# working.net
KiCad netlist of a schematic drawn in EAGLE
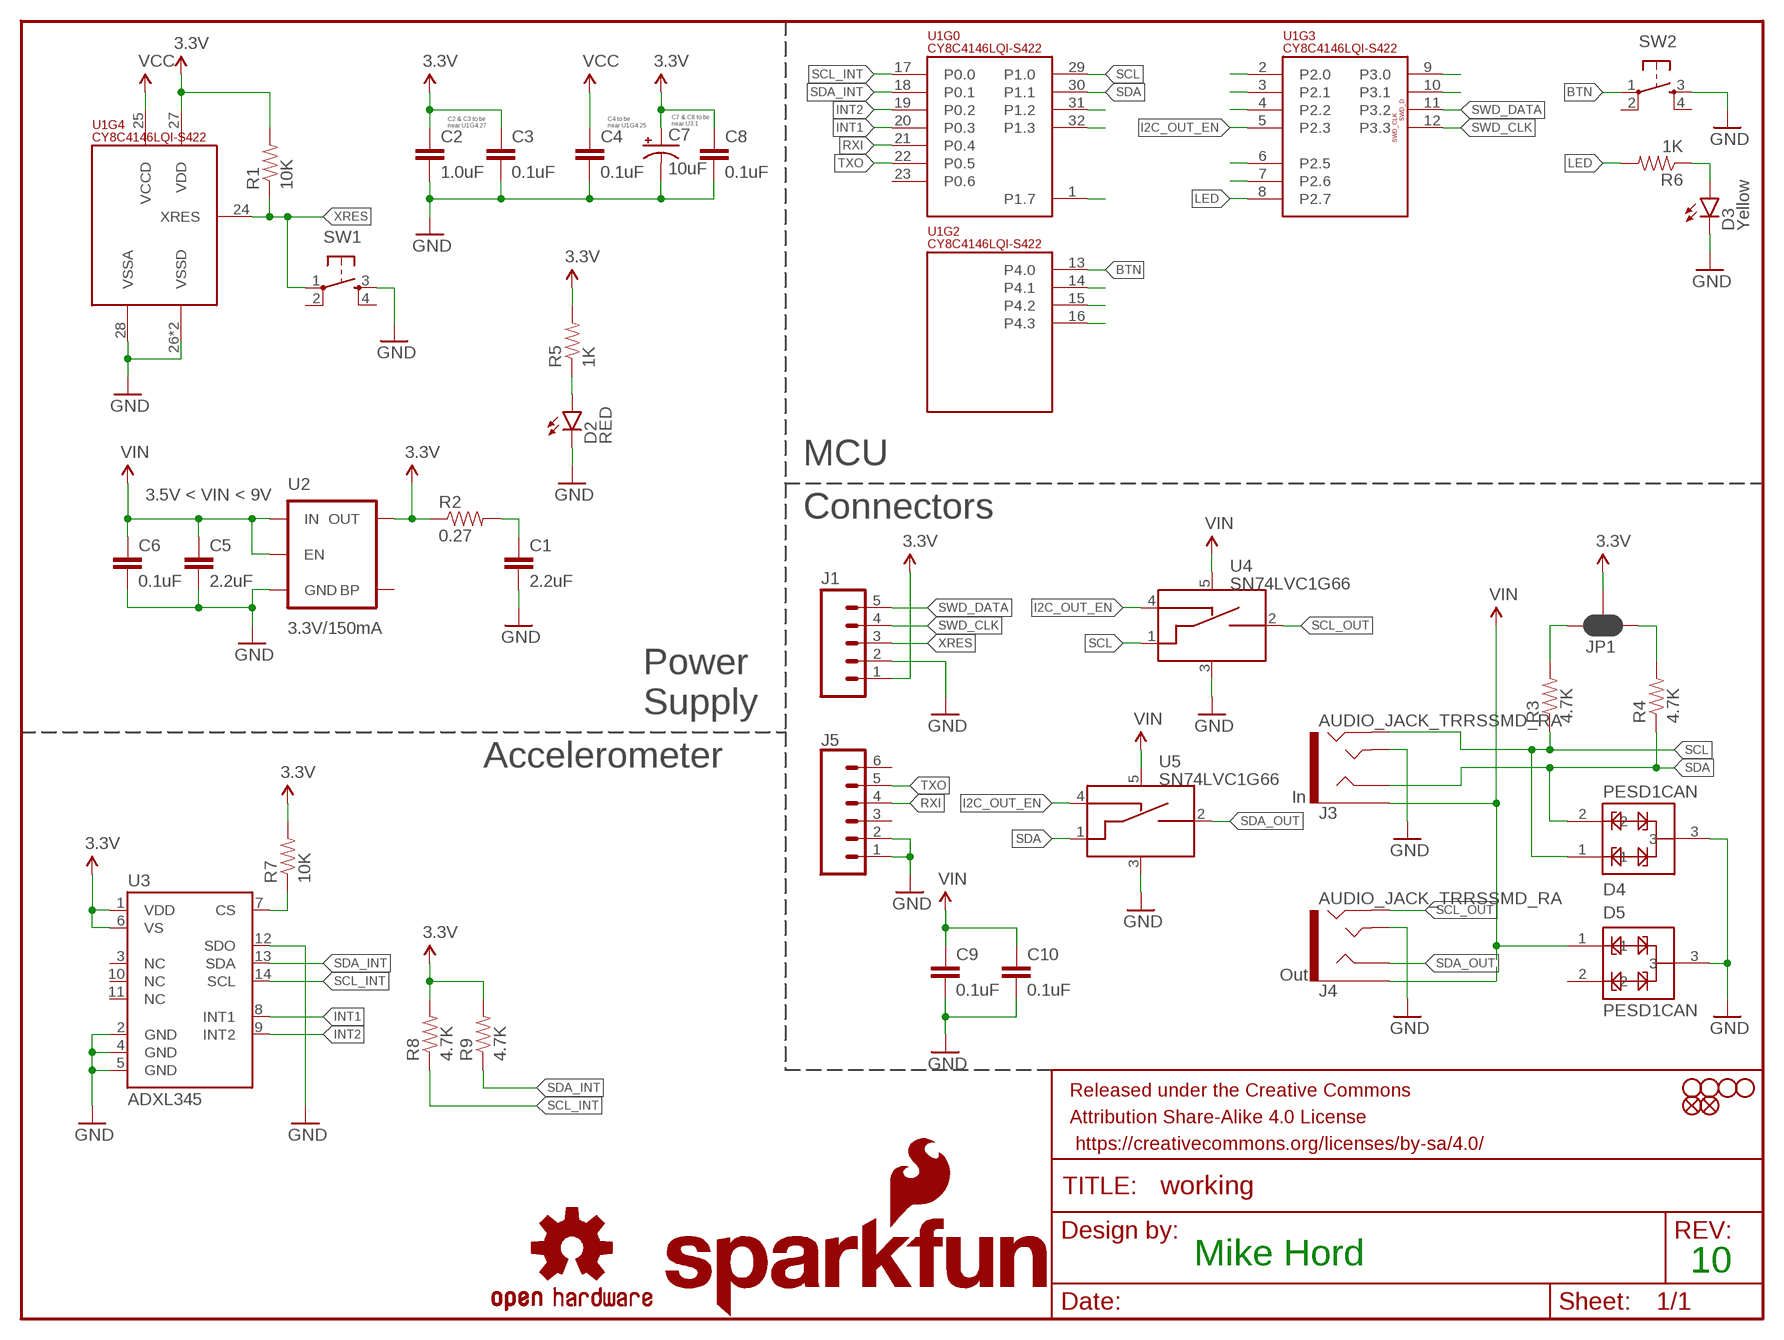
[diagram p0: schematic, sheet 1]

(export (version "E")
  (design (tool "Eeschema 10.0.6"))
  (components
    (comp (ref "C1")
      (value "2.2uF")
      (footprint "eagle-import:0603-CAP")
      (libsource (lib "eagle-import") (part "2.2UF-10V-20%(0603)"))
    )
    (comp (ref "C2")
      (value "1.0uF")
      (footprint "eagle-import:0402-CAP")
      (libsource (lib "eagle-import") (part "1.0UF-16V-10%(0402)"))
    )
    (comp (ref "C3")
      (value "0.1uF")
      (footprint "eagle-import:0402-CAP")
      (libsource (lib "eagle-import") (part "0.1UF-16V(+-10%)(0402)"))
    )
    (comp (ref "C4")
      (value "0.1uF")
      (footprint "eagle-import:0402-CAP")
      (libsource (lib "eagle-import") (part "0.1UF-16V(+-10%)(0402)"))
    )
    (comp (ref "C5")
      (value "2.2uF")
      (footprint "eagle-import:0603-CAP")
      (libsource (lib "eagle-import") (part "2.2UF-10V-20%(0603)"))
    )
    (comp (ref "C6")
      (value "0.1uF")
      (footprint "eagle-import:0402-CAP")
      (libsource (lib "eagle-import") (part "0.1UF-16V(+-10%)(0402)"))
    )
    (comp (ref "C7")
      (value "10uF")
      (footprint "eagle-import:EIA3216")
      (libsource (lib "eagle-import") (part "10UF-16V-10%(TANT)"))
    )
    (comp (ref "C8")
      (value "0.1uF")
      (footprint "eagle-import:0402-CAP")
      (libsource (lib "eagle-import") (part "0.1UF-16V(+-10%)(0402)"))
    )
    (comp (ref "C9")
      (value "0.1uF")
      (footprint "eagle-import:0402-CAP")
      (libsource (lib "eagle-import") (part "0.1UF-16V(+-10%)(0402)"))
    )
    (comp (ref "C10")
      (value "0.1uF")
      (footprint "eagle-import:0402-CAP")
      (libsource (lib "eagle-import") (part "0.1UF-16V(+-10%)(0402)"))
    )
    (comp (ref "D2")
      (value "RED")
      (footprint "eagle-import:LED-0603")
      (libsource (lib "eagle-import") (part "LED-RED0603"))
    )
    (comp (ref "D3")
      (value "Yellow")
      (footprint "eagle-import:LED-0603")
      (libsource (lib "eagle-import") (part "LED-YELLOW0603-SMART"))
    )
    (comp (ref "D4")
      (value "PESD1CAN")
      (footprint "eagle-import:SOT23-3")
      (libsource (lib "eagle-import") (part "PESD1CAN"))
    )
    (comp (ref "D5")
      (value "PESD1CAN")
      (footprint "eagle-import:SOT23-3")
      (libsource (lib "eagle-import") (part "PESD1CAN"))
    )
    (comp (ref "FD1")
      (value "FIDUCIALUFIDUCIAL")
      (footprint "eagle-import:MICRO-FIDUCIAL")
      (libsource (lib "eagle-import") (part "FIDUCIALUFIDUCIAL"))
    )
    (comp (ref "FD2")
      (value "FIDUCIALUFIDUCIAL")
      (footprint "eagle-import:MICRO-FIDUCIAL")
      (libsource (lib "eagle-import") (part "FIDUCIALUFIDUCIAL"))
    )
    (comp (ref "FRAME1")
      (value "FRAME-LETTER")
      (footprint "eagle-import:CREATIVE_COMMONS")
      (libsource (lib "eagle-import") (part "FRAME-LETTER"))
    )
    (comp (ref "H1")
      (value "STAND-OFF")
      (footprint "eagle-import:STAND-OFF")
      (libsource (lib "eagle-import") (part "STAND-OFF"))
    )
    (comp (ref "H2")
      (value "STAND-OFF")
      (footprint "eagle-import:STAND-OFF")
      (libsource (lib "eagle-import") (part "STAND-OFF"))
    )
    (comp (ref "H3")
      (value "STAND-OFF")
      (footprint "eagle-import:STAND-OFF")
      (libsource (lib "eagle-import") (part "STAND-OFF"))
    )
    (comp (ref "H4")
      (value "STAND-OFF")
      (footprint "eagle-import:STAND-OFF")
      (libsource (lib "eagle-import") (part "STAND-OFF"))
    )
    (comp (ref "J1")
      (value "M05NO_SILK")
      (footprint "eagle-import:1X05_NO_SILK")
      (libsource (lib "eagle-import") (part "M05NO_SILK"))
    )
    (comp (ref "J3")
      (value "AUDIO_JACK_TRRSSMD_RA")
      (footprint "eagle-import:AUDIO_JACK_3.5MM_TRRS_SMD_RA")
      (libsource (lib "eagle-import") (part "AUDIO_JACK_TRRSSMD_RA"))
    )
    (comp (ref "J4")
      (value "AUDIO_JACK_TRRSSMD_RA")
      (footprint "eagle-import:AUDIO_JACK_3.5MM_TRRS_SMD_RA")
      (libsource (lib "eagle-import") (part "AUDIO_JACK_TRRSSMD_RA"))
    )
    (comp (ref "J5")
      (value "CONN_06NO_SILK_NO_POP")
      (footprint "eagle-import:1X06_NO_SILK")
      (libsource (lib "eagle-import") (part "CONN_06NO_SILK_NO_POP"))
    )
    (comp (ref "JP1")
      (value "JUMPER-PAD-3-NC_BY_PASTE")
      (footprint "eagle-import:PAD-JUMPER-3-NC_BY_PASTE_YES_SILK_FULL_BOX")
      (libsource (lib "eagle-import") (part "JUMPER-PAD-3-NC_BY_PASTE"))
    )
    (comp (ref "LOGO1")
      (value "SFE_LOGO_NAME_FLAME.1_INCH")
      (footprint "eagle-import:SFE_LOGO_NAME_FLAME_.1")
      (libsource (lib "eagle-import") (part "SFE_LOGO_NAME_FLAME.1_INCH"))
    )
    (comp (ref "LOGO2")
      (value "OSHW-LOGOS")
      (footprint "eagle-import:OSHW-LOGO-S")
      (libsource (lib "eagle-import") (part "OSHW-LOGOS"))
    )
    (comp (ref "LOGO3")
      (value "OSHW-LOGOS")
      (footprint "eagle-import:OSHW-LOGO-S")
      (libsource (lib "eagle-import") (part "OSHW-LOGOS"))
    )
    (comp (ref "LOGO4")
      (value "SFE_LOGO_NAME_FLAME.1_INCH")
      (footprint "eagle-import:SFE_LOGO_NAME_FLAME_.1")
      (libsource (lib "eagle-import") (part "SFE_LOGO_NAME_FLAME.1_INCH"))
    )
    (comp (ref "R1")
      (value "10K")
      (footprint "eagle-import:0603-RES")
      (libsource (lib "eagle-import") (part "10KOHM-1/10W-1%(0603)0603"))
    )
    (comp (ref "R2")
      (value "0.27")
      (footprint "eagle-import:0603-RES")
      (libsource (lib "eagle-import") (part "0.27OHM-1/10W-1%(0603)"))
    )
    (comp (ref "R3")
      (value "4.7K")
      (footprint "eagle-import:0603-RES")
      (libsource (lib "eagle-import") (part "4.7KOHM-1/10W-1%(0603)"))
    )
    (comp (ref "R4")
      (value "4.7K")
      (footprint "eagle-import:0603-RES")
      (libsource (lib "eagle-import") (part "4.7KOHM-1/10W-1%(0603)"))
    )
    (comp (ref "R5")
      (value "1K")
      (footprint "eagle-import:0603-RES")
      (libsource (lib "eagle-import") (part "1KOHM-1/10W-1%(0603)"))
    )
    (comp (ref "R6")
      (value "1K")
      (footprint "eagle-import:0603-RES")
      (libsource (lib "eagle-import") (part "1KOHM-1/10W-1%(0603)"))
    )
    (comp (ref "R7")
      (value "10K")
      (footprint "eagle-import:0603-RES")
      (libsource (lib "eagle-import") (part "10KOHM-1/10W-1%(0603)0603"))
    )
    (comp (ref "R8")
      (value "4.7K")
      (footprint "eagle-import:0603-RES")
      (libsource (lib "eagle-import") (part "4.7KOHM-1/10W-1%(0603)"))
    )
    (comp (ref "R9")
      (value "4.7K")
      (footprint "eagle-import:0603-RES")
      (libsource (lib "eagle-import") (part "4.7KOHM-1/10W-1%(0603)"))
    )
    (comp (ref "SW1")
      (value "SWITCH_SPST_4_PINRECT")
      (footprint "eagle-import:TACTILE_SWITCH_SMD_4.6X2.8MM")
      (libsource (lib "eagle-import") (part "SWITCH_SPST_4_PINRECT"))
    )
    (comp (ref "SW2")
      (value "SWITCH_SPST_4_PINRECT")
      (footprint "eagle-import:TACTILE_SWITCH_SMD_4.6X2.8MM")
      (libsource (lib "eagle-import") (part "SWITCH_SPST_4_PINRECT"))
    )
    (comp (ref "U1")
      (value "CY8C4146LQI-S422")
      (footprint "eagle-import:QFN-32")
      (libsource (lib "eagle-import") (part "PSOC4_4100S_32QFN"))
    )
    (comp (ref "U2")
      (value "3.3V/150mA")
      (footprint "eagle-import:SOT23-5")
      (libsource (lib "eagle-import") (part "V_REG_MIC52053.3V"))
    )
    (comp (ref "U3")
      (value "ADXL345")
      (footprint "eagle-import:ADXL3451_1")
      (libsource (lib "eagle-import") (part "ADXL345{dblquote}"))
    )
    (comp (ref "U4")
      (value "SN74LVC1G66")
      (footprint "eagle-import:SOT23-5")
      (libsource (lib "eagle-import") (part "SN74LVC1G66_SPST_AMUX"))
    )
    (comp (ref "U5")
      (value "SN74LVC1G66")
      (footprint "eagle-import:SOT23-5")
      (libsource (lib "eagle-import") (part "SN74LVC1G66_SPST_AMUX"))
    )
  )
  (nets
    (net (code "1") (name "3.3V") (class "Default")
      (node (ref "C2") (pin "1") (pinfunction "1_1") (pintype "passive"))
      (node (ref "C3") (pin "1") (pinfunction "1_1") (pintype "passive"))
      (node (ref "C7") (pin "A") (pinfunction "+_A") (pintype "passive"))
      (node (ref "C8") (pin "1") (pinfunction "1_1") (pintype "passive"))
      (node (ref "J1") (pin "1") (pinfunction "1_1") (pintype "passive"))
      (node (ref "JP1") (pin "2") (pinfunction "2_2") (pintype "passive"))
      (node (ref "R1") (pin "2") (pinfunction "2_2") (pintype "passive"))
      (node (ref "R2") (pin "1") (pinfunction "1_1") (pintype "passive"))
      (node (ref "R5") (pin "2") (pinfunction "2_2") (pintype "passive"))
      (node (ref "R7") (pin "2") (pinfunction "2_2") (pintype "passive"))
      (node (ref "R8") (pin "2") (pinfunction "2_2") (pintype "passive"))
      (node (ref "R9") (pin "2") (pinfunction "2_2") (pintype "passive"))
      (node (ref "U1") (pin "27") (pinfunction "VDD_27") (pintype "bidirectional"))
      (node (ref "U2") (pin "5") (pinfunction "OUT_5") (pintype "passive"))
      (node (ref "U3") (pin "1") (pinfunction "VDD_1") (pintype "bidirectional"))
      (node (ref "U3") (pin "6") (pinfunction "VS_6") (pintype "bidirectional"))
    )
    (net (code "2") (name "BTN") (class "Default")
      (node (ref "SW2") (pin "1") (pinfunction "1_1") (pintype "passive"))
      (node (ref "U1") (pin "13") (pinfunction "P4.0_13") (pintype "bidirectional"))
    )
    (net (code "3") (name "GND") (class "Default")
      (node (ref "C1") (pin "2") (pinfunction "2_2") (pintype "passive"))
      (node (ref "C10") (pin "2") (pinfunction "2_2") (pintype "passive"))
      (node (ref "C2") (pin "2") (pinfunction "2_2") (pintype "passive"))
      (node (ref "C3") (pin "2") (pinfunction "2_2") (pintype "passive"))
      (node (ref "C4") (pin "2") (pinfunction "2_2") (pintype "passive"))
      (node (ref "C5") (pin "2") (pinfunction "2_2") (pintype "passive"))
      (node (ref "C6") (pin "2") (pinfunction "2_2") (pintype "passive"))
      (node (ref "C7") (pin "C") (pinfunction "-_C") (pintype "passive"))
      (node (ref "C8") (pin "2") (pinfunction "2_2") (pintype "passive"))
      (node (ref "C9") (pin "2") (pinfunction "2_2") (pintype "passive"))
      (node (ref "D2") (pin "C") (pinfunction "C_C") (pintype "passive"))
      (node (ref "D3") (pin "C") (pinfunction "C_C") (pintype "passive"))
      (node (ref "D4") (pin "3") (pinfunction "3_3") (pintype "bidirectional"))
      (node (ref "D5") (pin "3") (pinfunction "3_3") (pintype "bidirectional"))
      (node (ref "J1") (pin "2") (pinfunction "2_2") (pintype "passive"))
      (node (ref "J3") (pin "TIP") (pinfunction "TIP_TIP") (pintype "bidirectional"))
      (node (ref "J4") (pin "TIP") (pinfunction "TIP_TIP") (pintype "bidirectional"))
      (node (ref "J5") (pin "1") (pinfunction "1_1") (pintype "passive"))
      (node (ref "J5") (pin "2") (pinfunction "2_2") (pintype "passive"))
      (node (ref "SW1") (pin "3") (pinfunction "3_3") (pintype "passive"))
      (node (ref "SW2") (pin "3") (pinfunction "3_3") (pintype "passive"))
      (node (ref "U1") (pin "26") (pinfunction "VSSD_26") (pintype "bidirectional"))
      (node (ref "U1") (pin "28") (pinfunction "VSSA_28") (pintype "bidirectional"))
      (node (ref "U1") (pin "EP") (pinfunction "VSSD_EP") (pintype "bidirectional"))
      (node (ref "U2") (pin "2") (pinfunction "GND_2") (pintype "input"))
      (node (ref "U3") (pin "12") (pinfunction "SDO_12") (pintype "bidirectional"))
      (node (ref "U3") (pin "2") (pinfunction "GND_2") (pintype "bidirectional"))
      (node (ref "U3") (pin "4") (pinfunction "GND_4") (pintype "bidirectional"))
      (node (ref "U3") (pin "5") (pinfunction "GND_5") (pintype "bidirectional"))
      (node (ref "U4") (pin "3") (pinfunction "VSS_3") (pintype "bidirectional"))
      (node (ref "U5") (pin "3") (pinfunction "VSS_3") (pintype "bidirectional"))
    )
    (net (code "4") (name "I2C_OUT_EN") (class "Default")
      (node (ref "U1") (pin "5") (pinfunction "P2.3_5") (pintype "bidirectional"))
      (node (ref "U4") (pin "4") (pinfunction "CTRL_IN_4") (pintype "bidirectional"))
      (node (ref "U5") (pin "4") (pinfunction "CTRL_IN_4") (pintype "bidirectional"))
    )
    (net (code "5") (name "INT1") (class "Default")
      (node (ref "U1") (pin "20") (pinfunction "P0.3_20") (pintype "bidirectional"))
      (node (ref "U3") (pin "8") (pinfunction "INT1_8") (pintype "bidirectional"))
    )
    (net (code "6") (name "INT2") (class "Default")
      (node (ref "U1") (pin "19") (pinfunction "P0.2_19") (pintype "bidirectional"))
      (node (ref "U3") (pin "9") (pinfunction "INT2_9") (pintype "bidirectional"))
    )
    (net (code "7") (name "LED") (class "Default")
      (node (ref "R6") (pin "2") (pinfunction "2_2") (pintype "passive"))
      (node (ref "U1") (pin "8") (pinfunction "P2.7_8") (pintype "bidirectional"))
    )
    (net (code "8") (name "Net-(C1-Pad1)") (class "Default")
      (node (ref "C1") (pin "1") (pinfunction "1_1") (pintype "passive"))
      (node (ref "R2") (pin "2") (pinfunction "2_2") (pintype "passive"))
    )
    (net (code "9") (name "Net-(D2-PadA)") (class "Default")
      (node (ref "D2") (pin "A") (pinfunction "A_A") (pintype "passive"))
      (node (ref "R5") (pin "1") (pinfunction "1_1") (pintype "passive"))
    )
    (net (code "10") (name "Net-(D3-PadA)") (class "Default")
      (node (ref "D3") (pin "A") (pinfunction "A_A") (pintype "passive"))
      (node (ref "R6") (pin "1") (pinfunction "1_1") (pintype "passive"))
    )
    (net (code "11") (name "Net-(JP1-Pad1)") (class "Default")
      (node (ref "JP1") (pin "1") (pinfunction "1_1") (pintype "passive"))
      (node (ref "R4") (pin "2") (pinfunction "2_2") (pintype "passive"))
    )
    (net (code "12") (name "Net-(JP1-Pad3)") (class "Default")
      (node (ref "JP1") (pin "3") (pinfunction "3_3") (pintype "passive"))
      (node (ref "R3") (pin "2") (pinfunction "2_2") (pintype "passive"))
    )
    (net (code "13") (name "Net-(U3-CS)") (class "Default")
      (node (ref "R7") (pin "1") (pinfunction "1_1") (pintype "passive"))
      (node (ref "U3") (pin "7") (pinfunction "CS_7") (pintype "bidirectional"))
    )
    (net (code "14") (name "RXI") (class "Default")
      (node (ref "J5") (pin "4") (pinfunction "4_4") (pintype "passive"))
      (node (ref "U1") (pin "21") (pinfunction "P0.4_21") (pintype "bidirectional"))
    )
    (net (code "15") (name "SCL") (class "Default")
      (node (ref "D4") (pin "1") (pinfunction "1_1") (pintype "bidirectional"))
      (node (ref "J3") (pin "RING2") (pinfunction "RING2_RING2") (pintype "bidirectional"))
      (node (ref "R3") (pin "1") (pinfunction "1_1") (pintype "passive"))
      (node (ref "U1") (pin "29") (pinfunction "P1.0_29") (pintype "bidirectional"))
      (node (ref "U4") (pin "1") (pinfunction "A_IN_1") (pintype "bidirectional"))
    )
    (net (code "16") (name "SCL_INT") (class "Default")
      (node (ref "R8") (pin "1") (pinfunction "1_1") (pintype "passive"))
      (node (ref "U1") (pin "17") (pinfunction "P0.0_17") (pintype "bidirectional"))
      (node (ref "U3") (pin "14") (pinfunction "SCL_14") (pintype "bidirectional"))
    )
    (net (code "17") (name "SCL_OUT") (class "Default")
      (node (ref "J4") (pin "RING2") (pinfunction "RING2_RING2") (pintype "bidirectional"))
      (node (ref "U4") (pin "2") (pinfunction "A_OUT_2") (pintype "bidirectional"))
    )
    (net (code "18") (name "SDA") (class "Default")
      (node (ref "D4") (pin "2") (pinfunction "2_2") (pintype "bidirectional"))
      (node (ref "J3") (pin "RING1") (pinfunction "RING1_RING1") (pintype "bidirectional"))
      (node (ref "R4") (pin "1") (pinfunction "1_1") (pintype "passive"))
      (node (ref "U1") (pin "30") (pinfunction "P1.1_30") (pintype "bidirectional"))
      (node (ref "U5") (pin "1") (pinfunction "A_IN_1") (pintype "bidirectional"))
    )
    (net (code "19") (name "SDA_INT") (class "Default")
      (node (ref "R9") (pin "1") (pinfunction "1_1") (pintype "passive"))
      (node (ref "U1") (pin "18") (pinfunction "P0.1_18") (pintype "bidirectional"))
      (node (ref "U3") (pin "13") (pinfunction "SDA_13") (pintype "bidirectional"))
    )
    (net (code "20") (name "SDA_OUT") (class "Default")
      (node (ref "J4") (pin "RING1") (pinfunction "RING1_RING1") (pintype "bidirectional"))
      (node (ref "U5") (pin "2") (pinfunction "A_OUT_2") (pintype "bidirectional"))
    )
    (net (code "21") (name "SWD_CLK") (class "Default")
      (node (ref "J1") (pin "4") (pinfunction "4_4") (pintype "passive"))
      (node (ref "U1") (pin "12") (pinfunction "P3.3_12") (pintype "bidirectional"))
    )
    (net (code "22") (name "SWD_DATA") (class "Default")
      (node (ref "J1") (pin "5") (pinfunction "5_5") (pintype "passive"))
      (node (ref "U1") (pin "11") (pinfunction "P3.2_11") (pintype "bidirectional"))
    )
    (net (code "23") (name "TXO") (class "Default")
      (node (ref "J5") (pin "5") (pinfunction "5_5") (pintype "passive"))
      (node (ref "U1") (pin "22") (pinfunction "P0.5_22") (pintype "bidirectional"))
    )
    (net (code "24") (name "VCC") (class "Default")
      (node (ref "C4") (pin "1") (pinfunction "1_1") (pintype "passive"))
      (node (ref "U1") (pin "25") (pinfunction "VCCD_25") (pintype "bidirectional"))
    )
    (net (code "25") (name "VIN") (class "Default")
      (node (ref "C10") (pin "1") (pinfunction "1_1") (pintype "passive"))
      (node (ref "C5") (pin "1") (pinfunction "1_1") (pintype "passive"))
      (node (ref "C6") (pin "1") (pinfunction "1_1") (pintype "passive"))
      (node (ref "C9") (pin "1") (pinfunction "1_1") (pintype "passive"))
      (node (ref "D5") (pin "1") (pinfunction "1_1") (pintype "bidirectional"))
      (node (ref "J3") (pin "EARTH") (pinfunction "EARTH_EARTH") (pintype "bidirectional"))
      (node (ref "J4") (pin "EARTH") (pinfunction "EARTH_EARTH") (pintype "bidirectional"))
      (node (ref "U2") (pin "1") (pinfunction "IN_1") (pintype "input"))
      (node (ref "U2") (pin "3") (pinfunction "EN_3") (pintype "input"))
      (node (ref "U4") (pin "5") (pinfunction "VCC_5") (pintype "bidirectional"))
      (node (ref "U5") (pin "5") (pinfunction "VCC_5") (pintype "bidirectional"))
    )
    (net (code "26") (name "XRES") (class "Default")
      (node (ref "J1") (pin "3") (pinfunction "3_3") (pintype "passive"))
      (node (ref "R1") (pin "1") (pinfunction "1_1") (pintype "passive"))
      (node (ref "SW1") (pin "1") (pinfunction "1_1") (pintype "passive"))
      (node (ref "U1") (pin "24") (pinfunction "XRES_24") (pintype "bidirectional"))
    )
    (net (code "27") (name "unconnected-(D5-Pad2)") (class "Default")
      (node (ref "D5") (pin "2") (pinfunction "2_2") (pintype "bidirectional"))
    )
    (net (code "28") (name "unconnected-(J5-Pad3)") (class "Default")
      (node (ref "J5") (pin "3") (pinfunction "3_3") (pintype "passive"))
    )
    (net (code "29") (name "unconnected-(J5-Pad6)") (class "Default")
      (node (ref "J5") (pin "6") (pinfunction "6_6") (pintype "passive"))
    )
    (net (code "30") (name "unconnected-(SW1-Pad2)") (class "Default")
      (node (ref "SW1") (pin "2") (pinfunction "2_2") (pintype "passive"))
    )
    (net (code "31") (name "unconnected-(SW1-Pad4)") (class "Default")
      (node (ref "SW1") (pin "4") (pinfunction "4_4") (pintype "passive"))
    )
    (net (code "32") (name "unconnected-(SW2-Pad2)") (class "Default")
      (node (ref "SW2") (pin "2") (pinfunction "2_2") (pintype "passive"))
    )
    (net (code "33") (name "unconnected-(SW2-Pad4)") (class "Default")
      (node (ref "SW2") (pin "4") (pinfunction "4_4") (pintype "passive"))
    )
    (net (code "34") (name "unconnected-(U1A-P0.6-Pad23)") (class "Default")
      (node (ref "U1") (pin "23") (pinfunction "P0.6_23") (pintype "bidirectional"))
    )
    (net (code "35") (name "unconnected-(U1A-P1.2-Pad31)") (class "Default")
      (node (ref "U1") (pin "31") (pinfunction "P1.2_31") (pintype "bidirectional"))
    )
    (net (code "36") (name "unconnected-(U1A-P1.3-Pad32)") (class "Default")
      (node (ref "U1") (pin "32") (pinfunction "P1.3_32") (pintype "bidirectional"))
    )
    (net (code "37") (name "unconnected-(U1A-P1.7-Pad1)") (class "Default")
      (node (ref "U1") (pin "1") (pinfunction "P1.7_1") (pintype "bidirectional"))
    )
    (net (code "38") (name "unconnected-(U1B-P4.1-Pad14)") (class "Default")
      (node (ref "U1") (pin "14") (pinfunction "P4.1_14") (pintype "bidirectional"))
    )
    (net (code "39") (name "unconnected-(U1B-P4.2-Pad15)") (class "Default")
      (node (ref "U1") (pin "15") (pinfunction "P4.2_15") (pintype "bidirectional"))
    )
    (net (code "40") (name "unconnected-(U1B-P4.3-Pad16)") (class "Default")
      (node (ref "U1") (pin "16") (pinfunction "P4.3_16") (pintype "bidirectional"))
    )
    (net (code "41") (name "unconnected-(U1C-P2.0-Pad2)") (class "Default")
      (node (ref "U1") (pin "2") (pinfunction "P2.0_2") (pintype "bidirectional"))
    )
    (net (code "42") (name "unconnected-(U1C-P2.1-Pad3)") (class "Default")
      (node (ref "U1") (pin "3") (pinfunction "P2.1_3") (pintype "bidirectional"))
    )
    (net (code "43") (name "unconnected-(U1C-P2.2-Pad4)") (class "Default")
      (node (ref "U1") (pin "4") (pinfunction "P2.2_4") (pintype "bidirectional"))
    )
    (net (code "44") (name "unconnected-(U1C-P2.5-Pad6)") (class "Default")
      (node (ref "U1") (pin "6") (pinfunction "P2.5_6") (pintype "bidirectional"))
    )
    (net (code "45") (name "unconnected-(U1C-P2.6-Pad7)") (class "Default")
      (node (ref "U1") (pin "7") (pinfunction "P2.6_7") (pintype "bidirectional"))
    )
    (net (code "46") (name "unconnected-(U1C-P3.0-Pad9)") (class "Default")
      (node (ref "U1") (pin "9") (pinfunction "P3.0_9") (pintype "bidirectional"))
    )
    (net (code "47") (name "unconnected-(U1C-P3.1-Pad10)") (class "Default")
      (node (ref "U1") (pin "10") (pinfunction "P3.1_10") (pintype "bidirectional"))
    )
    (net (code "48") (name "unconnected-(U2-BP-Pad4)") (class "Default")
      (node (ref "U2") (pin "4") (pinfunction "BP_4") (pintype "input"))
    )
    (net (code "49") (name "unconnected-(U3-NC-Pad3)") (class "Default")
      (node (ref "U3") (pin "3") (pinfunction "NC_3") (pintype "bidirectional"))
    )
    (net (code "50") (name "unconnected-(U3-NC-Pad10)") (class "Default")
      (node (ref "U3") (pin "10") (pinfunction "NC_10") (pintype "bidirectional"))
    )
    (net (code "51") (name "unconnected-(U3-NC-Pad11)") (class "Default")
      (node (ref "U3") (pin "11") (pinfunction "NC_11") (pintype "bidirectional"))
    )
  )
)
